# hapcan-dali.net
KiCad netlist of a schematic drawn in EAGLE
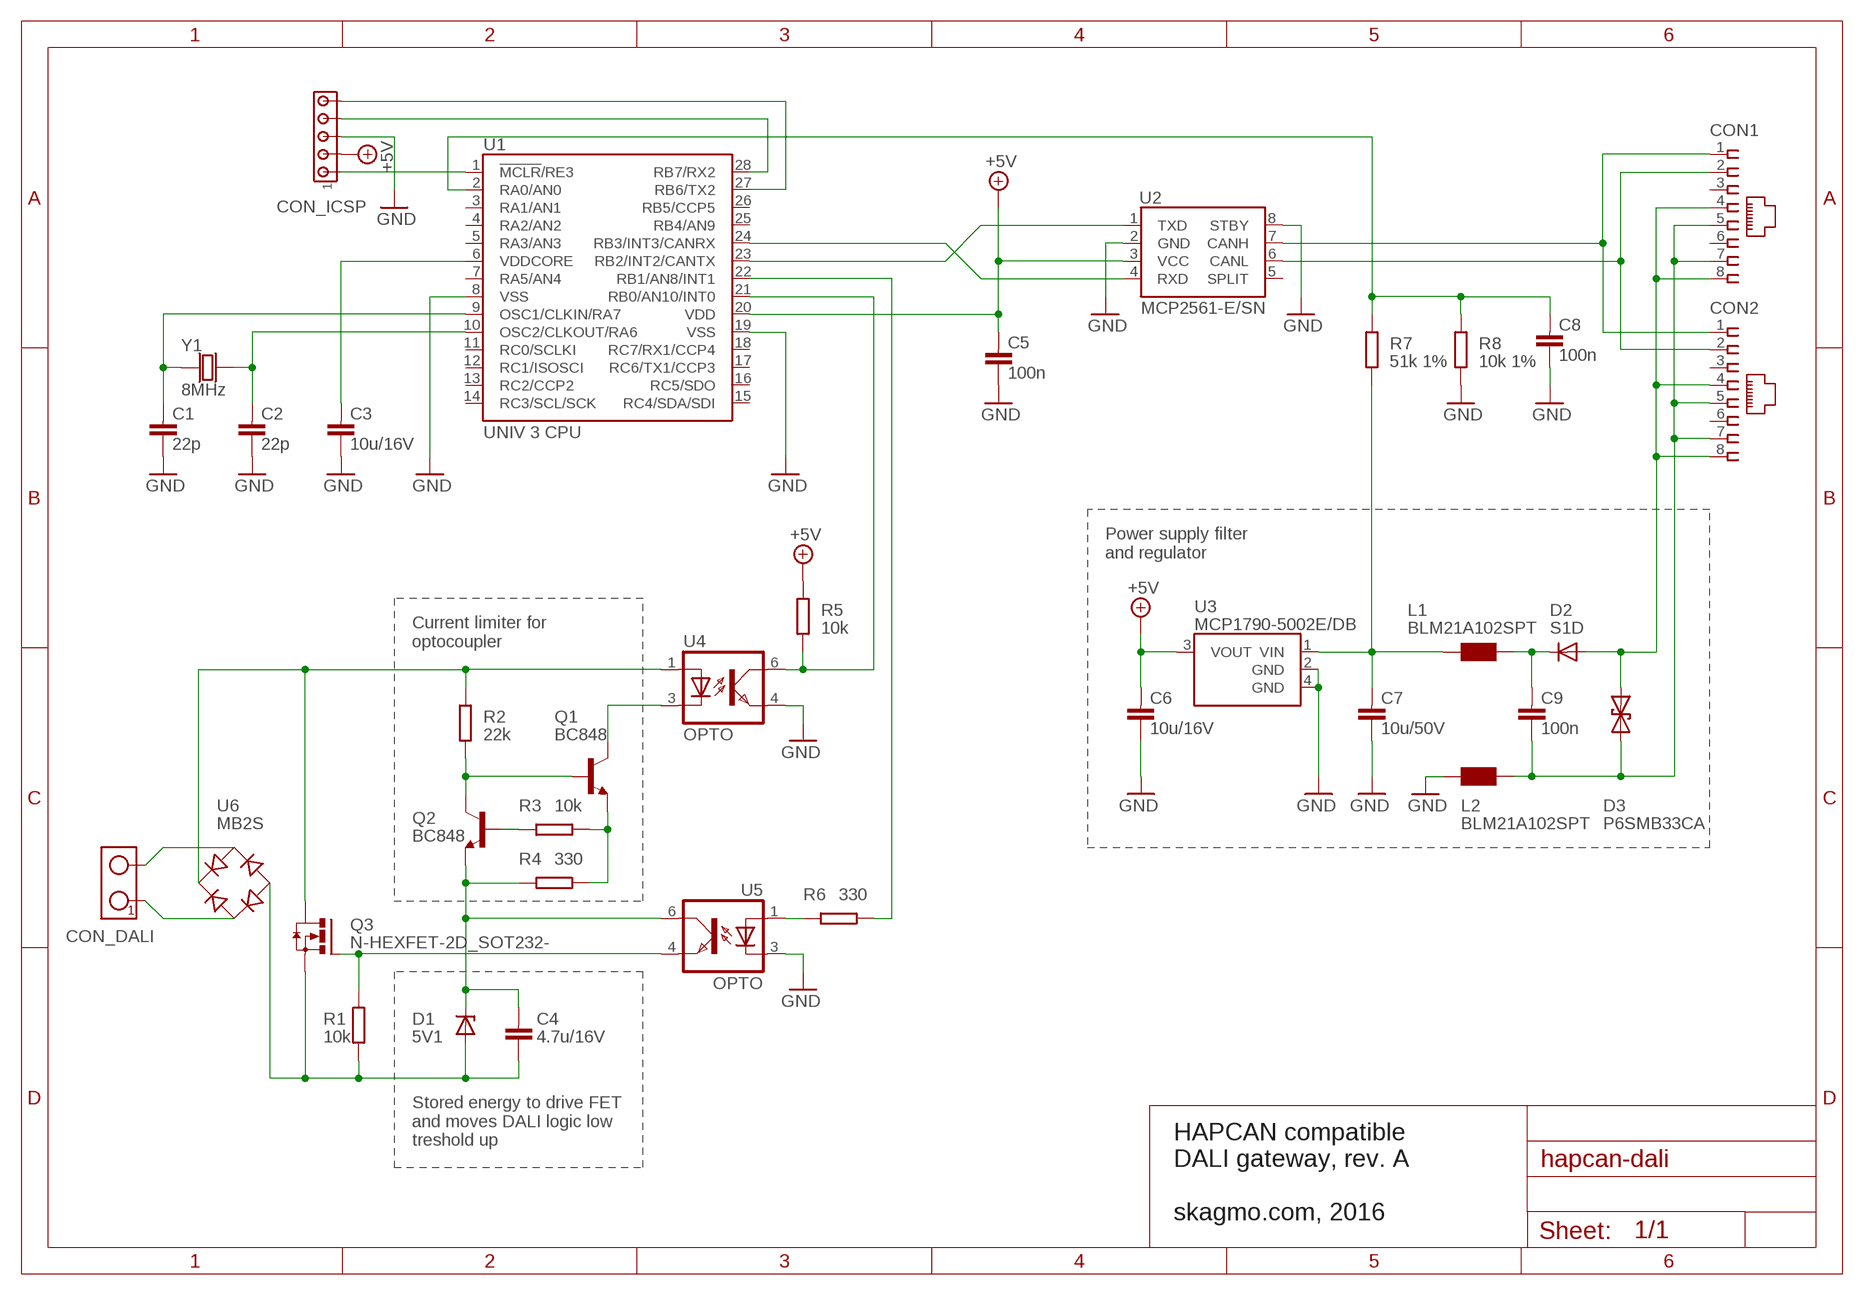
[diagram p0: schematic, sheet 1]

(export (version "E")
  (design (tool "Eeschema 10.0.6"))
  (components
    (comp (ref "C1")
      (value "22p")
      (footprint "eagle-import:0805")
      (libsource (lib "eagle-import") (part "CAPACITOR0805"))
    )
    (comp (ref "C2")
      (value "22p")
      (footprint "eagle-import:0805")
      (libsource (lib "eagle-import") (part "CAPACITOR0805"))
    )
    (comp (ref "C3")
      (value "10u/16V")
      (footprint "eagle-import:0805")
      (libsource (lib "eagle-import") (part "CAPACITOR0805"))
    )
    (comp (ref "C4")
      (value "4.7u/16V")
      (footprint "eagle-import:0805")
      (libsource (lib "eagle-import") (part "CAPACITOR0805"))
    )
    (comp (ref "C5")
      (value "100n")
      (footprint "eagle-import:0805")
      (libsource (lib "eagle-import") (part "CAPACITOR0805"))
    )
    (comp (ref "C6")
      (value "10u/16V")
      (footprint "eagle-import:0805")
      (libsource (lib "eagle-import") (part "CAPACITOR0805"))
    )
    (comp (ref "C7")
      (value "10u/50V")
      (footprint "eagle-import:1210")
      (libsource (lib "eagle-import") (part "CAPACITOR1210"))
    )
    (comp (ref "C8")
      (value "100n")
      (footprint "eagle-import:0805")
      (libsource (lib "eagle-import") (part "CAPACITOR0805"))
    )
    (comp (ref "C9")
      (value "100n")
      (footprint "eagle-import:0805")
      (libsource (lib "eagle-import") (part "CAPACITOR0805"))
    )
    (comp (ref "CON1")
      (value "RJ45-SOCKET")
      (footprint "eagle-import:RJ45-PCB-SOCKET")
      (libsource (lib "eagle-import") (part "RJ45-SOCKET"))
    )
    (comp (ref "CON2")
      (value "RJ45-SOCKET")
      (footprint "eagle-import:RJ45-PCB-SOCKET")
      (libsource (lib "eagle-import") (part "RJ45-SOCKET"))
    )
    (comp (ref "CON_DALI")
      (value "TERMINAL-2")
      (footprint "eagle-import:ARK2-5X10,5MM")
      (libsource (lib "eagle-import") (part "TERMINAL-2-5X10,5MM"))
    )
    (comp (ref "CON_ICSP")
      (value "HEADER5")
      (footprint "eagle-import:SIP-5")
      (libsource (lib "eagle-import") (part "HEADER5"))
    )
    (comp (ref "D1")
      (value "5V1")
      (footprint "eagle-import:SOT23")
      (libsource (lib "eagle-import") (part "ZENER-DIODESOT23"))
    )
    (comp (ref "D2")
      (value "S1D")
      (footprint "eagle-import:DO-214")
      (libsource (lib "eagle-import") (part "DIODE_DO-214"))
    )
    (comp (ref "D3")
      (value "P6SMB33CA")
      (footprint "eagle-import:DO-214_TRANSIL2")
      (libsource (lib "eagle-import") (part "DIODE_TRANSIL2"))
    )
    (comp (ref "L1")
      (value "BLM21A102SPT")
      (footprint "eagle-import:0805")
      (libsource (lib "eagle-import") (part "CHOKE0805"))
    )
    (comp (ref "L2")
      (value "BLM21A102SPT")
      (footprint "eagle-import:0805")
      (libsource (lib "eagle-import") (part "CHOKE0805"))
    )
    (comp (ref "Q1")
      (value "BC848")
      (footprint "eagle-import:SOT23")
      (libsource (lib "eagle-import") (part "BC848"))
    )
    (comp (ref "Q2")
      (value "BC848")
      (footprint "eagle-import:SOT23")
      (libsource (lib "eagle-import") (part "BC848"))
    )
    (comp (ref "Q3")
      (value "N-HEXFET-2D_SOT232-")
      (footprint "eagle-import:SOT223")
      (libsource (lib "eagle-import") (part "N-HEXFET-2D_?-SOT232"))
    )
    (comp (ref "R1")
      (value "10k")
      (footprint "eagle-import:0805")
      (libsource (lib "eagle-import") (part "RESISTOR0805"))
    )
    (comp (ref "R2")
      (value "22k")
      (footprint "eagle-import:0805")
      (libsource (lib "eagle-import") (part "RESISTOR0805"))
    )
    (comp (ref "R3")
      (value "10k")
      (footprint "eagle-import:0805")
      (libsource (lib "eagle-import") (part "RESISTOR0805"))
    )
    (comp (ref "R4")
      (value "330")
      (footprint "eagle-import:0805")
      (libsource (lib "eagle-import") (part "RESISTOR0805"))
    )
    (comp (ref "R5")
      (value "10k")
      (footprint "eagle-import:0805")
      (libsource (lib "eagle-import") (part "RESISTOR0805"))
    )
    (comp (ref "R6")
      (value "330")
      (footprint "eagle-import:0805")
      (libsource (lib "eagle-import") (part "RESISTOR0805"))
    )
    (comp (ref "R7")
      (value "51k 1%")
      (footprint "eagle-import:0805")
      (libsource (lib "eagle-import") (part "RESISTOR0805"))
    )
    (comp (ref "R8")
      (value "10k 1%")
      (footprint "eagle-import:0805")
      (libsource (lib "eagle-import") (part "RESISTOR0805"))
    )
    (comp (ref "U1")
      (value "UNIV 3 CPU")
      (footprint "eagle-import:UNIV3CPU")
      (libsource (lib "eagle-import") (part "UNIV3CPU"))
    )
    (comp (ref "U2")
      (value "MCP2561-E/SN")
      (footprint "eagle-import:SO-08")
      (libsource (lib "eagle-import") (part "MCP2561-E/SN"))
    )
    (comp (ref "U3")
      (value "MCP1790-5002E/DB")
      (footprint "eagle-import:SOT-223")
      (libsource (lib "eagle-import") (part "MCP1790"))
    )
    (comp (ref "U4")
      (value "OPTO")
      (footprint "eagle-import:TLP185")
      (libsource (lib "eagle-import") (part "OPTO"))
    )
    (comp (ref "U5")
      (value "OPTO")
      (footprint "eagle-import:TLP185")
      (libsource (lib "eagle-import") (part "OPTO"))
    )
    (comp (ref "U6")
      (value "MB2S")
      (footprint "eagle-import:SOIC-4")
      (libsource (lib "eagle-import") (part "MBS2"))
    )
    (comp (ref "Y1")
      (value "8MHz")
      (footprint "eagle-import:CRYSTAL-HC49V")
      (libsource (lib "eagle-import") (part "CRYSTAL-HC49V"))
    )
  )
  (nets
    (net (code "1") (name "+5V") (class "Default")
      (node (ref "C5") (pin "1") (pinfunction "1_1") (pintype "passive"))
      (node (ref "C6") (pin "1") (pinfunction "1_1") (pintype "passive"))
      (node (ref "CON_ICSP") (pin "2") (pinfunction "2_2") (pintype "passive"))
      (node (ref "R5") (pin "1") (pinfunction "1_1") (pintype "passive"))
      (node (ref "U1") (pin "20") (pinfunction "VDD_20") (pintype "bidirectional"))
      (node (ref "U2") (pin "3") (pinfunction "VCC_3") (pintype "bidirectional"))
      (node (ref "U3") (pin "3") (pinfunction "VOUT_3") (pintype "bidirectional"))
    )
    (net (code "2") (name "GND") (class "Default")
      (node (ref "C1") (pin "2") (pinfunction "2_2") (pintype "passive"))
      (node (ref "C2") (pin "2") (pinfunction "2_2") (pintype "passive"))
      (node (ref "C3") (pin "2") (pinfunction "2_2") (pintype "passive"))
      (node (ref "C5") (pin "2") (pinfunction "2_2") (pintype "passive"))
      (node (ref "C6") (pin "2") (pinfunction "2_2") (pintype "passive"))
      (node (ref "C7") (pin "2") (pinfunction "2_2") (pintype "passive"))
      (node (ref "C8") (pin "2") (pinfunction "2_2") (pintype "passive"))
      (node (ref "CON_ICSP") (pin "3") (pinfunction "3_3") (pintype "passive"))
      (node (ref "L2") (pin "1") (pinfunction "1_1") (pintype "passive"))
      (node (ref "R8") (pin "1") (pinfunction "1_1") (pintype "passive"))
      (node (ref "U1") (pin "19") (pinfunction "VSS_19") (pintype "bidirectional"))
      (node (ref "U1") (pin "8") (pinfunction "VSS_8") (pintype "bidirectional"))
      (node (ref "U2") (pin "2") (pinfunction "GND_2") (pintype "bidirectional"))
      (node (ref "U2") (pin "8") (pinfunction "STBY_8") (pintype "bidirectional"))
      (node (ref "U3") (pin "2") (pinfunction "GND_2") (pintype "bidirectional"))
      (node (ref "U3") (pin "4") (pinfunction "GND_4") (pintype "bidirectional"))
      (node (ref "U4") (pin "4") (pinfunction "EMIT_4") (pintype "passive"))
      (node (ref "U5") (pin "3") (pinfunction "C_3") (pintype "passive"))
    )
    (net (code "3") (name "Net-(C9-Pad1)") (class "Default")
      (node (ref "C9") (pin "1") (pinfunction "1_1") (pintype "passive"))
      (node (ref "D2") (pin "C") (pinfunction "C_C") (pintype "passive"))
      (node (ref "L1") (pin "2") (pinfunction "2_2") (pintype "passive"))
    )
    (net (code "4") (name "Net-(D1-A)") (class "Default")
      (node (ref "C4") (pin "2") (pinfunction "2_2") (pintype "passive"))
      (node (ref "D1") (pin "1") (pinfunction "A_1") (pintype "passive"))
      (node (ref "Q3") (pin "3") (pinfunction "S_3") (pintype "passive"))
      (node (ref "R1") (pin "1") (pinfunction "1_1") (pintype "passive"))
      (node (ref "U6") (pin "-") (pinfunction "-_-") (pintype "passive"))
    )
    (net (code "5") (name "Net-(D1-C)") (class "Default")
      (node (ref "C4") (pin "1") (pinfunction "1_1") (pintype "passive"))
      (node (ref "D1") (pin "3") (pinfunction "C_3") (pintype "passive"))
      (node (ref "Q2") (pin "2") (pinfunction "E_2") (pintype "passive"))
      (node (ref "R4") (pin "1") (pinfunction "1_1") (pintype "passive"))
      (node (ref "U5") (pin "6") (pinfunction "COL_6") (pintype "passive"))
    )
    (net (code "6") (name "Net-(D3-1)") (class "Default")
      (node (ref "C9") (pin "2") (pinfunction "2_2") (pintype "passive"))
      (node (ref "CON1") (pin "5") (pinfunction "5_5") (pintype "passive"))
      (node (ref "CON1") (pin "7") (pinfunction "7_7") (pintype "passive"))
      (node (ref "CON2") (pin "5") (pinfunction "5_5") (pintype "passive"))
      (node (ref "CON2") (pin "7") (pinfunction "7_7") (pintype "passive"))
      (node (ref "D3") (pin "A") (pinfunction "1_A") (pintype "passive"))
      (node (ref "L2") (pin "2") (pinfunction "2_2") (pintype "passive"))
    )
    (net (code "7") (name "Net-(D3-2)") (class "Default")
      (node (ref "CON1") (pin "4") (pinfunction "4_4") (pintype "passive"))
      (node (ref "CON1") (pin "8") (pinfunction "8_8") (pintype "passive"))
      (node (ref "CON2") (pin "4") (pinfunction "4_4") (pintype "passive"))
      (node (ref "CON2") (pin "8") (pinfunction "8_8") (pintype "passive"))
      (node (ref "D2") (pin "A") (pinfunction "A_A") (pintype "passive"))
      (node (ref "D3") (pin "C") (pinfunction "2_C") (pintype "passive"))
    )
    (net (code "8") (name "Net-(Q1-B)") (class "Default")
      (node (ref "Q1") (pin "1") (pinfunction "B_1") (pintype "passive"))
      (node (ref "Q2") (pin "3") (pinfunction "C_3") (pintype "passive"))
      (node (ref "R2") (pin "1") (pinfunction "1_1") (pintype "passive"))
    )
    (net (code "9") (name "Net-(Q1-C)") (class "Default")
      (node (ref "Q1") (pin "3") (pinfunction "C_3") (pintype "passive"))
      (node (ref "U4") (pin "3") (pinfunction "C_3") (pintype "passive"))
    )
    (net (code "10") (name "Net-(Q1-E)") (class "Default")
      (node (ref "Q1") (pin "2") (pinfunction "E_2") (pintype "passive"))
      (node (ref "R3") (pin "1") (pinfunction "1_1") (pintype "passive"))
      (node (ref "R4") (pin "2") (pinfunction "2_2") (pintype "passive"))
    )
    (net (code "11") (name "Net-(Q2-B)") (class "Default")
      (node (ref "Q2") (pin "1") (pinfunction "B_1") (pintype "passive"))
      (node (ref "R3") (pin "2") (pinfunction "2_2") (pintype "passive"))
    )
    (net (code "12") (name "Net-(Q3-G)") (class "Default")
      (node (ref "Q3") (pin "1") (pinfunction "G_1") (pintype "passive"))
      (node (ref "R1") (pin "2") (pinfunction "2_2") (pintype "passive"))
      (node (ref "U5") (pin "4") (pinfunction "EMIT_4") (pintype "passive"))
    )
    (net (code "13") (name "Net-(U1-OSC1{slash}CLKIN{slash}RA7)") (class "Default")
      (node (ref "C1") (pin "1") (pinfunction "1_1") (pintype "passive"))
      (node (ref "U1") (pin "9") (pinfunction "OSC1/CLKIN/RA7_9") (pintype "bidirectional"))
      (node (ref "Y1") (pin "1") (pinfunction "1_1") (pintype "passive"))
    )
    (net (code "14") (name "Net-(U1-OSC2{slash}CLKOUT{slash}RA6)") (class "Default")
      (node (ref "C2") (pin "1") (pinfunction "1_1") (pintype "passive"))
      (node (ref "U1") (pin "10") (pinfunction "OSC2/CLKOUT/RA6_10") (pintype "bidirectional"))
      (node (ref "Y1") (pin "2") (pinfunction "2_2") (pintype "passive"))
    )
    (net (code "15") (name "Net-(U1-RA0{slash}AN0)") (class "Default")
      (node (ref "C8") (pin "1") (pinfunction "1_1") (pintype "passive"))
      (node (ref "R7") (pin "2") (pinfunction "2_2") (pintype "passive"))
      (node (ref "R8") (pin "2") (pinfunction "2_2") (pintype "passive"))
      (node (ref "U1") (pin "2") (pinfunction "RA0/AN0_2") (pintype "bidirectional"))
    )
    (net (code "16") (name "Net-(U1-RB0{slash}AN10{slash}INT0)") (class "Default")
      (node (ref "R5") (pin "2") (pinfunction "2_2") (pintype "passive"))
      (node (ref "U1") (pin "21") (pinfunction "RB0/AN10/INT0_21") (pintype "bidirectional"))
      (node (ref "U4") (pin "6") (pinfunction "COL_6") (pintype "passive"))
    )
    (net (code "17") (name "Net-(U1-RB1{slash}AN8{slash}INT1)") (class "Default")
      (node (ref "R6") (pin "1") (pinfunction "1_1") (pintype "passive"))
      (node (ref "U1") (pin "22") (pinfunction "RB1/AN8/INT1_22") (pintype "bidirectional"))
    )
    (net (code "18") (name "Net-(U1-RB2{slash}INT2{slash}CANTX)") (class "Default")
      (node (ref "U1") (pin "23") (pinfunction "RB2/INT2/CANTX_23") (pintype "bidirectional"))
      (node (ref "U2") (pin "1") (pinfunction "TXD_1") (pintype "bidirectional"))
    )
    (net (code "19") (name "Net-(U1-RB3{slash}INT3{slash}CANRX)") (class "Default")
      (node (ref "U1") (pin "24") (pinfunction "RB3/INT3/CANRX_24") (pintype "bidirectional"))
      (node (ref "U2") (pin "4") (pinfunction "RXD_4") (pintype "bidirectional"))
    )
    (net (code "20") (name "Net-(U1-RB6{slash}TX2)") (class "Default")
      (node (ref "CON_ICSP") (pin "5") (pinfunction "5_5") (pintype "passive"))
      (node (ref "U1") (pin "27") (pinfunction "RB6/TX2_27") (pintype "bidirectional"))
    )
    (net (code "21") (name "Net-(U1-RB7{slash}RX2)") (class "Default")
      (node (ref "CON_ICSP") (pin "4") (pinfunction "4_4") (pintype "passive"))
      (node (ref "U1") (pin "28") (pinfunction "RB7/RX2_28") (pintype "bidirectional"))
    )
    (net (code "22") (name "Net-(U1-VDDCORE)") (class "Default")
      (node (ref "C3") (pin "1") (pinfunction "1_1") (pintype "passive"))
      (node (ref "U1") (pin "6") (pinfunction "VDDCORE_6") (pintype "bidirectional"))
    )
    (net (code "23") (name "Net-(U1-~{MCLR}{slash}RE3)") (class "Default")
      (node (ref "CON_ICSP") (pin "1") (pinfunction "1_1") (pintype "passive"))
      (node (ref "U1") (pin "1") (pinfunction "~{MCLR}/RE3_1") (pintype "bidirectional"))
    )
    (net (code "24") (name "Net-(U2-CANH)") (class "Default")
      (node (ref "CON1") (pin "1") (pinfunction "1_1") (pintype "passive"))
      (node (ref "CON2") (pin "1") (pinfunction "1_1") (pintype "passive"))
      (node (ref "U2") (pin "7") (pinfunction "CANH_7") (pintype "bidirectional"))
    )
    (net (code "25") (name "Net-(U2-CANL)") (class "Default")
      (node (ref "CON1") (pin "2") (pinfunction "2_2") (pintype "passive"))
      (node (ref "CON2") (pin "2") (pinfunction "2_2") (pintype "passive"))
      (node (ref "U2") (pin "6") (pinfunction "CANL_6") (pintype "bidirectional"))
    )
    (net (code "26") (name "Net-(U3-VIN)") (class "Default")
      (node (ref "C7") (pin "1") (pinfunction "1_1") (pintype "passive"))
      (node (ref "L1") (pin "1") (pinfunction "1_1") (pintype "passive"))
      (node (ref "R7") (pin "1") (pinfunction "1_1") (pintype "passive"))
      (node (ref "U3") (pin "1") (pinfunction "VIN_1") (pintype "bidirectional"))
    )
    (net (code "27") (name "Net-(U4-A)") (class "Default")
      (node (ref "Q3") (pin "2") (pinfunction "D_2") (pintype "passive"))
      (node (ref "Q3") (pin "4") (pinfunction "D_4") (pintype "passive"))
      (node (ref "R2") (pin "2") (pinfunction "2_2") (pintype "passive"))
      (node (ref "U4") (pin "1") (pinfunction "A_1") (pintype "passive"))
      (node (ref "U6") (pin "+") (pinfunction "+_+") (pintype "passive"))
    )
    (net (code "28") (name "Net-(U5-A)") (class "Default")
      (node (ref "R6") (pin "2") (pinfunction "2_2") (pintype "passive"))
      (node (ref "U5") (pin "1") (pinfunction "A_1") (pintype "passive"))
    )
    (net (code "29") (name "Net-(U6-AC1)") (class "Default")
      (node (ref "CON_DALI") (pin "1") (pinfunction "1_1") (pintype "passive"))
      (node (ref "U6") (pin "~1") (pinfunction "AC1_~1") (pintype "passive"))
    )
    (net (code "30") (name "Net-(U6-AC2)") (class "Default")
      (node (ref "CON_DALI") (pin "2") (pinfunction "2_2") (pintype "passive"))
      (node (ref "U6") (pin "~2") (pinfunction "AC2_~2") (pintype "passive"))
    )
    (net (code "31") (name "unconnected-(CON1-Pad3)") (class "Default")
      (node (ref "CON1") (pin "3") (pinfunction "3_3") (pintype "passive"))
    )
    (net (code "32") (name "unconnected-(CON1-Pad6)") (class "Default")
      (node (ref "CON1") (pin "6") (pinfunction "6_6") (pintype "passive"))
    )
    (net (code "33") (name "unconnected-(CON2-Pad3)") (class "Default")
      (node (ref "CON2") (pin "3") (pinfunction "3_3") (pintype "passive"))
    )
    (net (code "34") (name "unconnected-(CON2-Pad6)") (class "Default")
      (node (ref "CON2") (pin "6") (pinfunction "6_6") (pintype "passive"))
    )
    (net (code "35") (name "unconnected-(U1-RA1{slash}AN1-Pad3)") (class "Default")
      (node (ref "U1") (pin "3") (pinfunction "RA1/AN1_3") (pintype "bidirectional"))
    )
    (net (code "36") (name "unconnected-(U1-RA2{slash}AN2-Pad4)") (class "Default")
      (node (ref "U1") (pin "4") (pinfunction "RA2/AN2_4") (pintype "bidirectional"))
    )
    (net (code "37") (name "unconnected-(U1-RA3{slash}AN3-Pad5)") (class "Default")
      (node (ref "U1") (pin "5") (pinfunction "RA3/AN3_5") (pintype "bidirectional"))
    )
    (net (code "38") (name "unconnected-(U1-RA5{slash}AN4-Pad7)") (class "Default")
      (node (ref "U1") (pin "7") (pinfunction "RA5/AN4_7") (pintype "bidirectional"))
    )
    (net (code "39") (name "unconnected-(U1-RB4{slash}AN9-Pad25)") (class "Default")
      (node (ref "U1") (pin "25") (pinfunction "RB4/AN9_25") (pintype "bidirectional"))
    )
    (net (code "40") (name "unconnected-(U1-RB5{slash}CCP5-Pad26)") (class "Default")
      (node (ref "U1") (pin "26") (pinfunction "RB5/CCP5_26") (pintype "bidirectional"))
    )
    (net (code "41") (name "unconnected-(U1-RC0{slash}SCLKI-Pad11)") (class "Default")
      (node (ref "U1") (pin "11") (pinfunction "RC0/SCLKI_11") (pintype "bidirectional"))
    )
    (net (code "42") (name "unconnected-(U1-RC1{slash}ISOSCI-Pad12)") (class "Default")
      (node (ref "U1") (pin "12") (pinfunction "RC1/ISOSCI_12") (pintype "bidirectional"))
    )
    (net (code "43") (name "unconnected-(U1-RC2{slash}CCP2-Pad13)") (class "Default")
      (node (ref "U1") (pin "13") (pinfunction "RC2/CCP2_13") (pintype "bidirectional"))
    )
    (net (code "44") (name "unconnected-(U1-RC3{slash}SCL{slash}SCK-Pad14)") (class "Default")
      (node (ref "U1") (pin "14") (pinfunction "RC3/SCL/SCK_14") (pintype "bidirectional"))
    )
    (net (code "45") (name "unconnected-(U1-RC4{slash}SDA{slash}SDI-Pad15)") (class "Default")
      (node (ref "U1") (pin "15") (pinfunction "RC4/SDA/SDI_15") (pintype "bidirectional"))
    )
    (net (code "46") (name "unconnected-(U1-RC5{slash}SDO-Pad16)") (class "Default")
      (node (ref "U1") (pin "16") (pinfunction "RC5/SDO_16") (pintype "bidirectional"))
    )
    (net (code "47") (name "unconnected-(U1-RC6{slash}TX1{slash}CCP3-Pad17)") (class "Default")
      (node (ref "U1") (pin "17") (pinfunction "RC6/TX1/CCP3_17") (pintype "bidirectional"))
    )
    (net (code "48") (name "unconnected-(U1-RC7{slash}RX1{slash}CCP4-Pad18)") (class "Default")
      (node (ref "U1") (pin "18") (pinfunction "RC7/RX1/CCP4_18") (pintype "bidirectional"))
    )
    (net (code "49") (name "unconnected-(U2-SPLIT-Pad5)") (class "Default")
      (node (ref "U2") (pin "5") (pinfunction "SPLIT_5") (pintype "bidirectional"))
    )
  )
)
